# design.net
KiCad netlist of a schematic drawn in EasyEDA
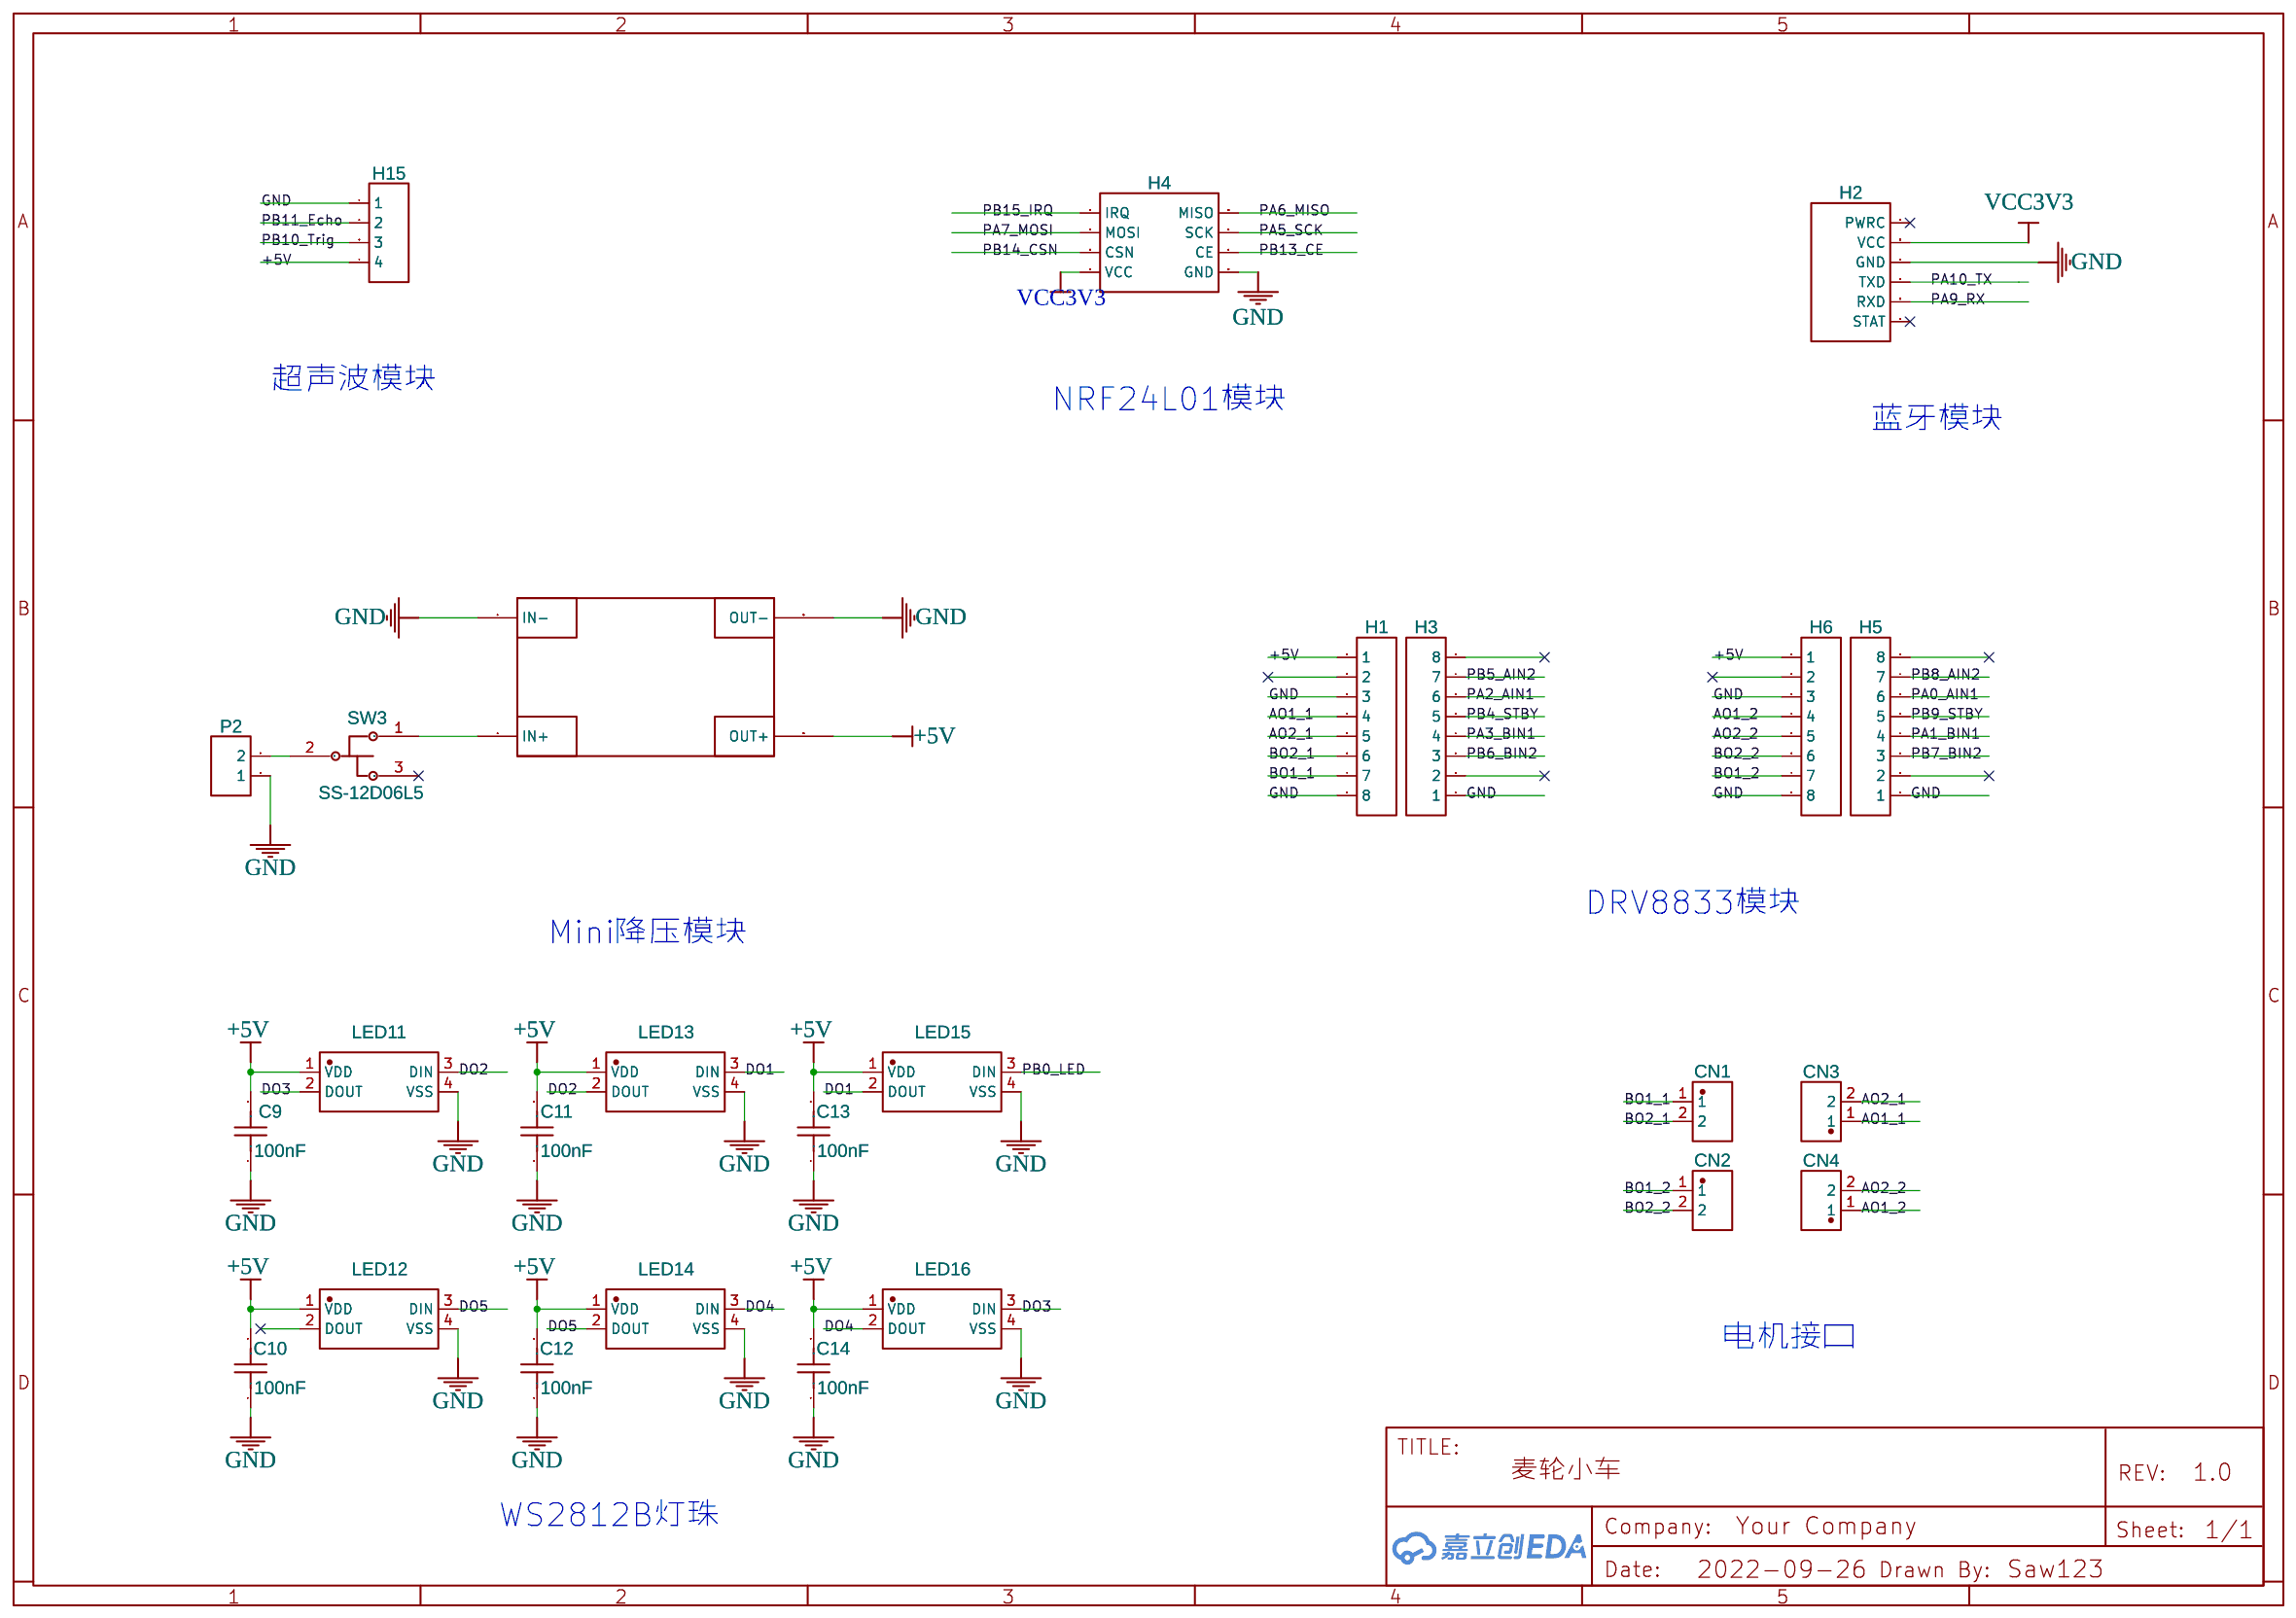
[diagram p0: schematic sheet]

(export (version "E")
  (design (tool "Eeschema 10.0.6"))
  (components
    (comp (ref "C9") (value "100nF") (libsource (lib "") (part "C_0805_US")))
    (comp (ref "C10") (value "100nF") (libsource (lib "") (part "C_0805_US")))
    (comp (ref "C11") (value "100nF") (libsource (lib "") (part "C_0805_US")))
    (comp (ref "C12") (value "100nF") (libsource (lib "") (part "C_0805_US")))
    (comp (ref "C13") (value "100nF") (libsource (lib "") (part "C_0805_US")))
    (comp (ref "C14") (value "100nF") (libsource (lib "") (part "C_0805_US")))
    (comp (ref "CN1")
      (value "HX25035-2A")
      (fields (field (name "BOM_Supplier Part") "C442378"))
      (libsource (lib "") (part "HX25035-2A_1"))
    )
    (comp (ref "CN2")
      (value "HX25035-2A")
      (fields (field (name "BOM_Supplier Part") "C442378"))
      (libsource (lib "") (part "HX25035-2A_1"))
    )
    (comp (ref "CN3")
      (value "HX25035-2A")
      (fields (field (name "BOM_Supplier Part") "C442378"))
      (libsource (lib "") (part "HX25035-2A"))
    )
    (comp (ref "CN4")
      (value "HX25035-2A")
      (fields (field (name "BOM_Supplier Part") "C442378"))
      (libsource (lib "") (part "HX25035-2A"))
    )
    (comp (ref "H1")
      (value "HDR-F-2.54_1x8")
      (fields (field (name "BOM_Supplier Part") "C225505"))
      (libsource (lib "") (part "HDR-F-2.54_1x8"))
    )
    (comp (ref "H2") (value "JDY-23蓝牙模块") (libsource (lib "") (part "JDY-23蓝牙模块")))
    (comp (ref "H3")
      (value "HDR-F-2.54_1x8")
      (fields (field (name "BOM_Supplier Part") "C225505"))
      (libsource (lib "") (part "HDR-F-2.54_1x8_1"))
    )
    (comp (ref "H4") (value "NRF24L01无线模块") (libsource (lib "") (part "NRF24L01无线模块")))
    (comp (ref "H5")
      (value "HDR-F-2.54_1x8")
      (fields (field (name "BOM_Supplier Part") "C225505"))
      (libsource (lib "") (part "HDR-F-2.54_1x8_1"))
    )
    (comp (ref "H6")
      (value "HDR-F-2.54_1x8")
      (fields (field (name "BOM_Supplier Part") "C225505"))
      (libsource (lib "") (part "HDR-F-2.54_1x8"))
    )
    (comp (ref "H15")
      (value "HDR-F-2.54_1x4")
      (fields (field (name "BOM_Supplier Part") "C225501"))
      (libsource (lib "") (part "HDR-F-2.54_1x4"))
    )
    (comp (ref "LED11")
      (value "WS2812B-V5/W")
      (fields (field (name "BOM_Supplier Part") "C2874885"))
      (libsource (lib "") (part "WS2812B-V5/W"))
    )
    (comp (ref "LED12")
      (value "WS2812B-V5/W")
      (fields (field (name "BOM_Supplier Part") "C2874885"))
      (libsource (lib "") (part "WS2812B-V5/W"))
    )
    (comp (ref "LED13")
      (value "WS2812B-V5/W")
      (fields (field (name "BOM_Supplier Part") "C2874885"))
      (libsource (lib "") (part "WS2812B-V5/W"))
    )
    (comp (ref "LED14")
      (value "WS2812B-V5/W")
      (fields (field (name "BOM_Supplier Part") "C2874885"))
      (libsource (lib "") (part "WS2812B-V5/W"))
    )
    (comp (ref "LED15")
      (value "WS2812B-V5/W")
      (fields (field (name "BOM_Supplier Part") "C2874885"))
      (libsource (lib "") (part "WS2812B-V5/W"))
    )
    (comp (ref "LED16")
      (value "WS2812B-V5/W")
      (fields (field (name "BOM_Supplier Part") "C2874885"))
      (libsource (lib "") (part "WS2812B-V5/W"))
    )
    (comp (ref "P2") (value "CONN-TH_2P-P5.00") (libsource (lib "") (part "CONN-TH_2P-P5.00")))
    (comp (ref "SW3")
      (value "SS-12D06L5")
      (fields (field (name "BOM_Supplier Part") "C319015"))
      (libsource (lib "") (part "SS-12D06L5"))
    )
    (comp (ref "U2") (value "Mini降压模块") (libsource (lib "") (part "Mini降压模块")))
  )
  (nets
    (net (code "1") (name "+5V") (class "Default")
      (node (ref "C10") (pin "2") (pinfunction "2_2") (pintype "unspecified"))
      (node (ref "C11") (pin "2") (pinfunction "2_2") (pintype "unspecified"))
      (node (ref "C12") (pin "2") (pinfunction "2_2") (pintype "unspecified"))
      (node (ref "C13") (pin "2") (pinfunction "2_2") (pintype "unspecified"))
      (node (ref "C14") (pin "2") (pinfunction "2_2") (pintype "unspecified"))
      (node (ref "C9") (pin "2") (pinfunction "2_2") (pintype "unspecified"))
      (node (ref "H1") (pin "1") (pinfunction "1_1") (pintype "unspecified"))
      (node (ref "H15") (pin "4") (pinfunction "4_4") (pintype "unspecified"))
      (node (ref "H6") (pin "1") (pinfunction "1_1") (pintype "unspecified"))
      (node (ref "LED11") (pin "1") (pinfunction "VDD_1") (pintype "unspecified"))
      (node (ref "LED12") (pin "1") (pinfunction "VDD_1") (pintype "unspecified"))
      (node (ref "LED13") (pin "1") (pinfunction "VDD_1") (pintype "unspecified"))
      (node (ref "LED14") (pin "1") (pinfunction "VDD_1") (pintype "unspecified"))
      (node (ref "LED15") (pin "1") (pinfunction "VDD_1") (pintype "unspecified"))
      (node (ref "LED16") (pin "1") (pinfunction "VDD_1") (pintype "unspecified"))
      (node (ref "U2") (pin "OUT+") (pinfunction "OUT+_OUT+") (pintype "unspecified"))
    )
    (net (code "2") (name "/AO1_1") (class "Default")
      (node (ref "CN3") (pin "1") (pinfunction "1_1") (pintype "unspecified"))
      (node (ref "H1") (pin "4") (pinfunction "4_4") (pintype "unspecified"))
    )
    (net (code "3") (name "/AO1_2") (class "Default")
      (node (ref "CN4") (pin "1") (pinfunction "1_1") (pintype "unspecified"))
      (node (ref "H6") (pin "4") (pinfunction "4_4") (pintype "unspecified"))
    )
    (net (code "4") (name "/AO2_1") (class "Default")
      (node (ref "CN3") (pin "2") (pinfunction "2_2") (pintype "unspecified"))
      (node (ref "H1") (pin "5") (pinfunction "5_5") (pintype "unspecified"))
    )
    (net (code "5") (name "/AO2_2") (class "Default")
      (node (ref "CN4") (pin "2") (pinfunction "2_2") (pintype "unspecified"))
      (node (ref "H6") (pin "5") (pinfunction "5_5") (pintype "unspecified"))
    )
    (net (code "6") (name "/BO1_1") (class "Default")
      (node (ref "CN1") (pin "1") (pinfunction "1_1") (pintype "unspecified"))
      (node (ref "H1") (pin "7") (pinfunction "7_7") (pintype "unspecified"))
    )
    (net (code "7") (name "/BO1_2") (class "Default")
      (node (ref "CN2") (pin "1") (pinfunction "1_1") (pintype "unspecified"))
      (node (ref "H6") (pin "7") (pinfunction "7_7") (pintype "unspecified"))
    )
    (net (code "8") (name "/BO2_1") (class "Default")
      (node (ref "CN1") (pin "2") (pinfunction "2_2") (pintype "unspecified"))
      (node (ref "H1") (pin "6") (pinfunction "6_6") (pintype "unspecified"))
    )
    (net (code "9") (name "/BO2_2") (class "Default")
      (node (ref "CN2") (pin "2") (pinfunction "2_2") (pintype "unspecified"))
      (node (ref "H6") (pin "6") (pinfunction "6_6") (pintype "unspecified"))
    )
    (net (code "10") (name "/DO1") (class "Default")
      (node (ref "LED13") (pin "3") (pinfunction "DIN_3") (pintype "unspecified"))
      (node (ref "LED15") (pin "2") (pinfunction "DOUT_2") (pintype "unspecified"))
    )
    (net (code "11") (name "/DO2") (class "Default")
      (node (ref "LED11") (pin "3") (pinfunction "DIN_3") (pintype "unspecified"))
      (node (ref "LED13") (pin "2") (pinfunction "DOUT_2") (pintype "unspecified"))
    )
    (net (code "12") (name "/DO3") (class "Default")
      (node (ref "LED11") (pin "2") (pinfunction "DOUT_2") (pintype "unspecified"))
      (node (ref "LED16") (pin "3") (pinfunction "DIN_3") (pintype "unspecified"))
    )
    (net (code "13") (name "/DO4") (class "Default")
      (node (ref "LED14") (pin "3") (pinfunction "DIN_3") (pintype "unspecified"))
      (node (ref "LED16") (pin "2") (pinfunction "DOUT_2") (pintype "unspecified"))
    )
    (net (code "14") (name "/DO5") (class "Default")
      (node (ref "LED12") (pin "3") (pinfunction "DIN_3") (pintype "unspecified"))
      (node (ref "LED14") (pin "2") (pinfunction "DOUT_2") (pintype "unspecified"))
    )
    (net (code "15") (name "/PA0_AIN1") (class "Default")
      (node (ref "H5") (pin "6") (pinfunction "6_6") (pintype "unspecified"))
    )
    (net (code "16") (name "/PA1_BIN1") (class "Default")
      (node (ref "H5") (pin "4") (pinfunction "4_4") (pintype "unspecified"))
    )
    (net (code "17") (name "/PA2_AIN1") (class "Default")
      (node (ref "H3") (pin "6") (pinfunction "6_6") (pintype "unspecified"))
    )
    (net (code "18") (name "/PA3_BIN1") (class "Default")
      (node (ref "H3") (pin "4") (pinfunction "4_4") (pintype "unspecified"))
    )
    (net (code "19") (name "/PA5_SCK") (class "Default")
      (node (ref "H4") (pin "SCK") (pinfunction "SCK_SCK") (pintype "unspecified"))
    )
    (net (code "20") (name "/PA6_MISO") (class "Default")
      (node (ref "H4") (pin "MISO") (pinfunction "MISO_MISO") (pintype "unspecified"))
    )
    (net (code "21") (name "/PA7_MOSI") (class "Default")
      (node (ref "H4") (pin "MOSI") (pinfunction "MOSI_MOSI") (pintype "unspecified"))
    )
    (net (code "22") (name "/PA9_RX") (class "Default")
      (node (ref "H2") (pin "RXD") (pinfunction "RXD_RXD") (pintype "input"))
    )
    (net (code "23") (name "/PA10_TX") (class "Default")
      (node (ref "H2") (pin "TXD") (pinfunction "TXD_TXD") (pintype "input"))
    )
    (net (code "24") (name "/PB0_LED") (class "Default")
      (node (ref "LED15") (pin "3") (pinfunction "DIN_3") (pintype "unspecified"))
    )
    (net (code "25") (name "/PB4_STBY") (class "Default")
      (node (ref "H3") (pin "5") (pinfunction "5_5") (pintype "unspecified"))
    )
    (net (code "26") (name "/PB5_AIN2") (class "Default")
      (node (ref "H3") (pin "7") (pinfunction "7_7") (pintype "unspecified"))
    )
    (net (code "27") (name "/PB6_BIN2") (class "Default")
      (node (ref "H3") (pin "3") (pinfunction "3_3") (pintype "unspecified"))
    )
    (net (code "28") (name "/PB7_BIN2") (class "Default")
      (node (ref "H5") (pin "3") (pinfunction "3_3") (pintype "unspecified"))
    )
    (net (code "29") (name "/PB8_AIN2") (class "Default")
      (node (ref "H5") (pin "7") (pinfunction "7_7") (pintype "unspecified"))
    )
    (net (code "30") (name "/PB9_STBY") (class "Default")
      (node (ref "H5") (pin "5") (pinfunction "5_5") (pintype "unspecified"))
    )
    (net (code "31") (name "/PB10_Trig") (class "Default")
      (node (ref "H15") (pin "3") (pinfunction "3_3") (pintype "unspecified"))
    )
    (net (code "32") (name "/PB11_Echo") (class "Default")
      (node (ref "H15") (pin "2") (pinfunction "2_2") (pintype "unspecified"))
    )
    (net (code "33") (name "/PB13_CE") (class "Default")
      (node (ref "H4") (pin "CE") (pinfunction "CE_CE") (pintype "unspecified"))
    )
    (net (code "34") (name "/PB14_CSN") (class "Default")
      (node (ref "H4") (pin "CSN") (pinfunction "CSN_CSN") (pintype "unspecified"))
    )
    (net (code "35") (name "/PB15_IRQ") (class "Default")
      (node (ref "H4") (pin "IRQ") (pinfunction "IRQ_IRQ") (pintype "unspecified"))
    )
    (net (code "36") (name "GND") (class "Default")
      (node (ref "C10") (pin "1") (pinfunction "1_1") (pintype "unspecified"))
      (node (ref "C11") (pin "1") (pinfunction "1_1") (pintype "unspecified"))
      (node (ref "C12") (pin "1") (pinfunction "1_1") (pintype "unspecified"))
      (node (ref "C13") (pin "1") (pinfunction "1_1") (pintype "unspecified"))
      (node (ref "C14") (pin "1") (pinfunction "1_1") (pintype "unspecified"))
      (node (ref "C9") (pin "1") (pinfunction "1_1") (pintype "unspecified"))
      (node (ref "H1") (pin "3") (pinfunction "3_3") (pintype "unspecified"))
      (node (ref "H1") (pin "8") (pinfunction "8_8") (pintype "unspecified"))
      (node (ref "H15") (pin "1") (pinfunction "1_1") (pintype "unspecified"))
      (node (ref "H2") (pin "GND") (pinfunction "GND_GND") (pintype "input"))
      (node (ref "H3") (pin "1") (pinfunction "1_1") (pintype "unspecified"))
      (node (ref "H4") (pin "GND") (pinfunction "GND_GND") (pintype "unspecified"))
      (node (ref "H5") (pin "1") (pinfunction "1_1") (pintype "unspecified"))
      (node (ref "H6") (pin "3") (pinfunction "3_3") (pintype "unspecified"))
      (node (ref "H6") (pin "8") (pinfunction "8_8") (pintype "unspecified"))
      (node (ref "LED11") (pin "4") (pinfunction "VSS_4") (pintype "unspecified"))
      (node (ref "LED12") (pin "4") (pinfunction "VSS_4") (pintype "unspecified"))
      (node (ref "LED13") (pin "4") (pinfunction "VSS_4") (pintype "unspecified"))
      (node (ref "LED14") (pin "4") (pinfunction "VSS_4") (pintype "unspecified"))
      (node (ref "LED15") (pin "4") (pinfunction "VSS_4") (pintype "unspecified"))
      (node (ref "LED16") (pin "4") (pinfunction "VSS_4") (pintype "unspecified"))
      (node (ref "P2") (pin "1") (pinfunction "1_1") (pintype "unspecified"))
      (node (ref "U2") (pin "IN-") (pinfunction "IN-_IN-") (pintype "unspecified"))
      (node (ref "U2") (pin "OUT-") (pinfunction "OUT-_OUT-") (pintype "unspecified"))
    )
    (net (code "37") (name "Net-(P2-Pad2)") (class "Default")
      (node (ref "P2") (pin "2") (pinfunction "2_2") (pintype "unspecified"))
      (node (ref "SW3") (pin "2") (pinfunction "2_2") (pintype "unspecified"))
    )
    (net (code "38") (name "Net-(SW3-Pad1)") (class "Default")
      (node (ref "SW3") (pin "1") (pinfunction "1_1") (pintype "unspecified"))
      (node (ref "U2") (pin "IN+") (pinfunction "IN+_IN+") (pintype "unspecified"))
    )
    (net (code "39") (name "VCC3V3") (class "Default")
      (node (ref "H2") (pin "VCC") (pinfunction "VCC_VCC") (pintype "input"))
      (node (ref "H4") (pin "VCC") (pinfunction "VCC_VCC") (pintype "unspecified"))
    )
    (net (code "40") (name "unconnected-(H1-Pad2)") (class "Default")
      (node (ref "H1") (pin "2") (pinfunction "2_2") (pintype "unspecified+no_connect"))
    )
    (net (code "41") (name "unconnected-(H2-PadPWRC)") (class "Default")
      (node (ref "H2") (pin "PWRC") (pinfunction "PWRC_PWRC") (pintype "input+no_connect"))
    )
    (net (code "42") (name "unconnected-(H2-PadSTAT)") (class "Default")
      (node (ref "H2") (pin "STAT") (pinfunction "STAT_STAT") (pintype "input+no_connect"))
    )
    (net (code "43") (name "unconnected-(H3-Pad2)") (class "Default")
      (node (ref "H3") (pin "2") (pinfunction "2_2") (pintype "unspecified+no_connect"))
    )
    (net (code "44") (name "unconnected-(H3-Pad8)") (class "Default")
      (node (ref "H3") (pin "8") (pinfunction "8_8") (pintype "unspecified+no_connect"))
    )
    (net (code "45") (name "unconnected-(H5-Pad2)") (class "Default")
      (node (ref "H5") (pin "2") (pinfunction "2_2") (pintype "unspecified+no_connect"))
    )
    (net (code "46") (name "unconnected-(H5-Pad8)") (class "Default")
      (node (ref "H5") (pin "8") (pinfunction "8_8") (pintype "unspecified+no_connect"))
    )
    (net (code "47") (name "unconnected-(H6-Pad2)") (class "Default")
      (node (ref "H6") (pin "2") (pinfunction "2_2") (pintype "unspecified+no_connect"))
    )
    (net (code "48") (name "unconnected-(LED12-DOUT-Pad2)") (class "Default")
      (node (ref "LED12") (pin "2") (pinfunction "DOUT_2") (pintype "unspecified+no_connect"))
    )
    (net (code "49") (name "unconnected-(SW3-Pad3)") (class "Default")
      (node (ref "SW3") (pin "3") (pinfunction "3_3") (pintype "unspecified+no_connect"))
    )
  )
)
